# 4G.net
KiCad netlist of a schematic drawn in Altium Designer
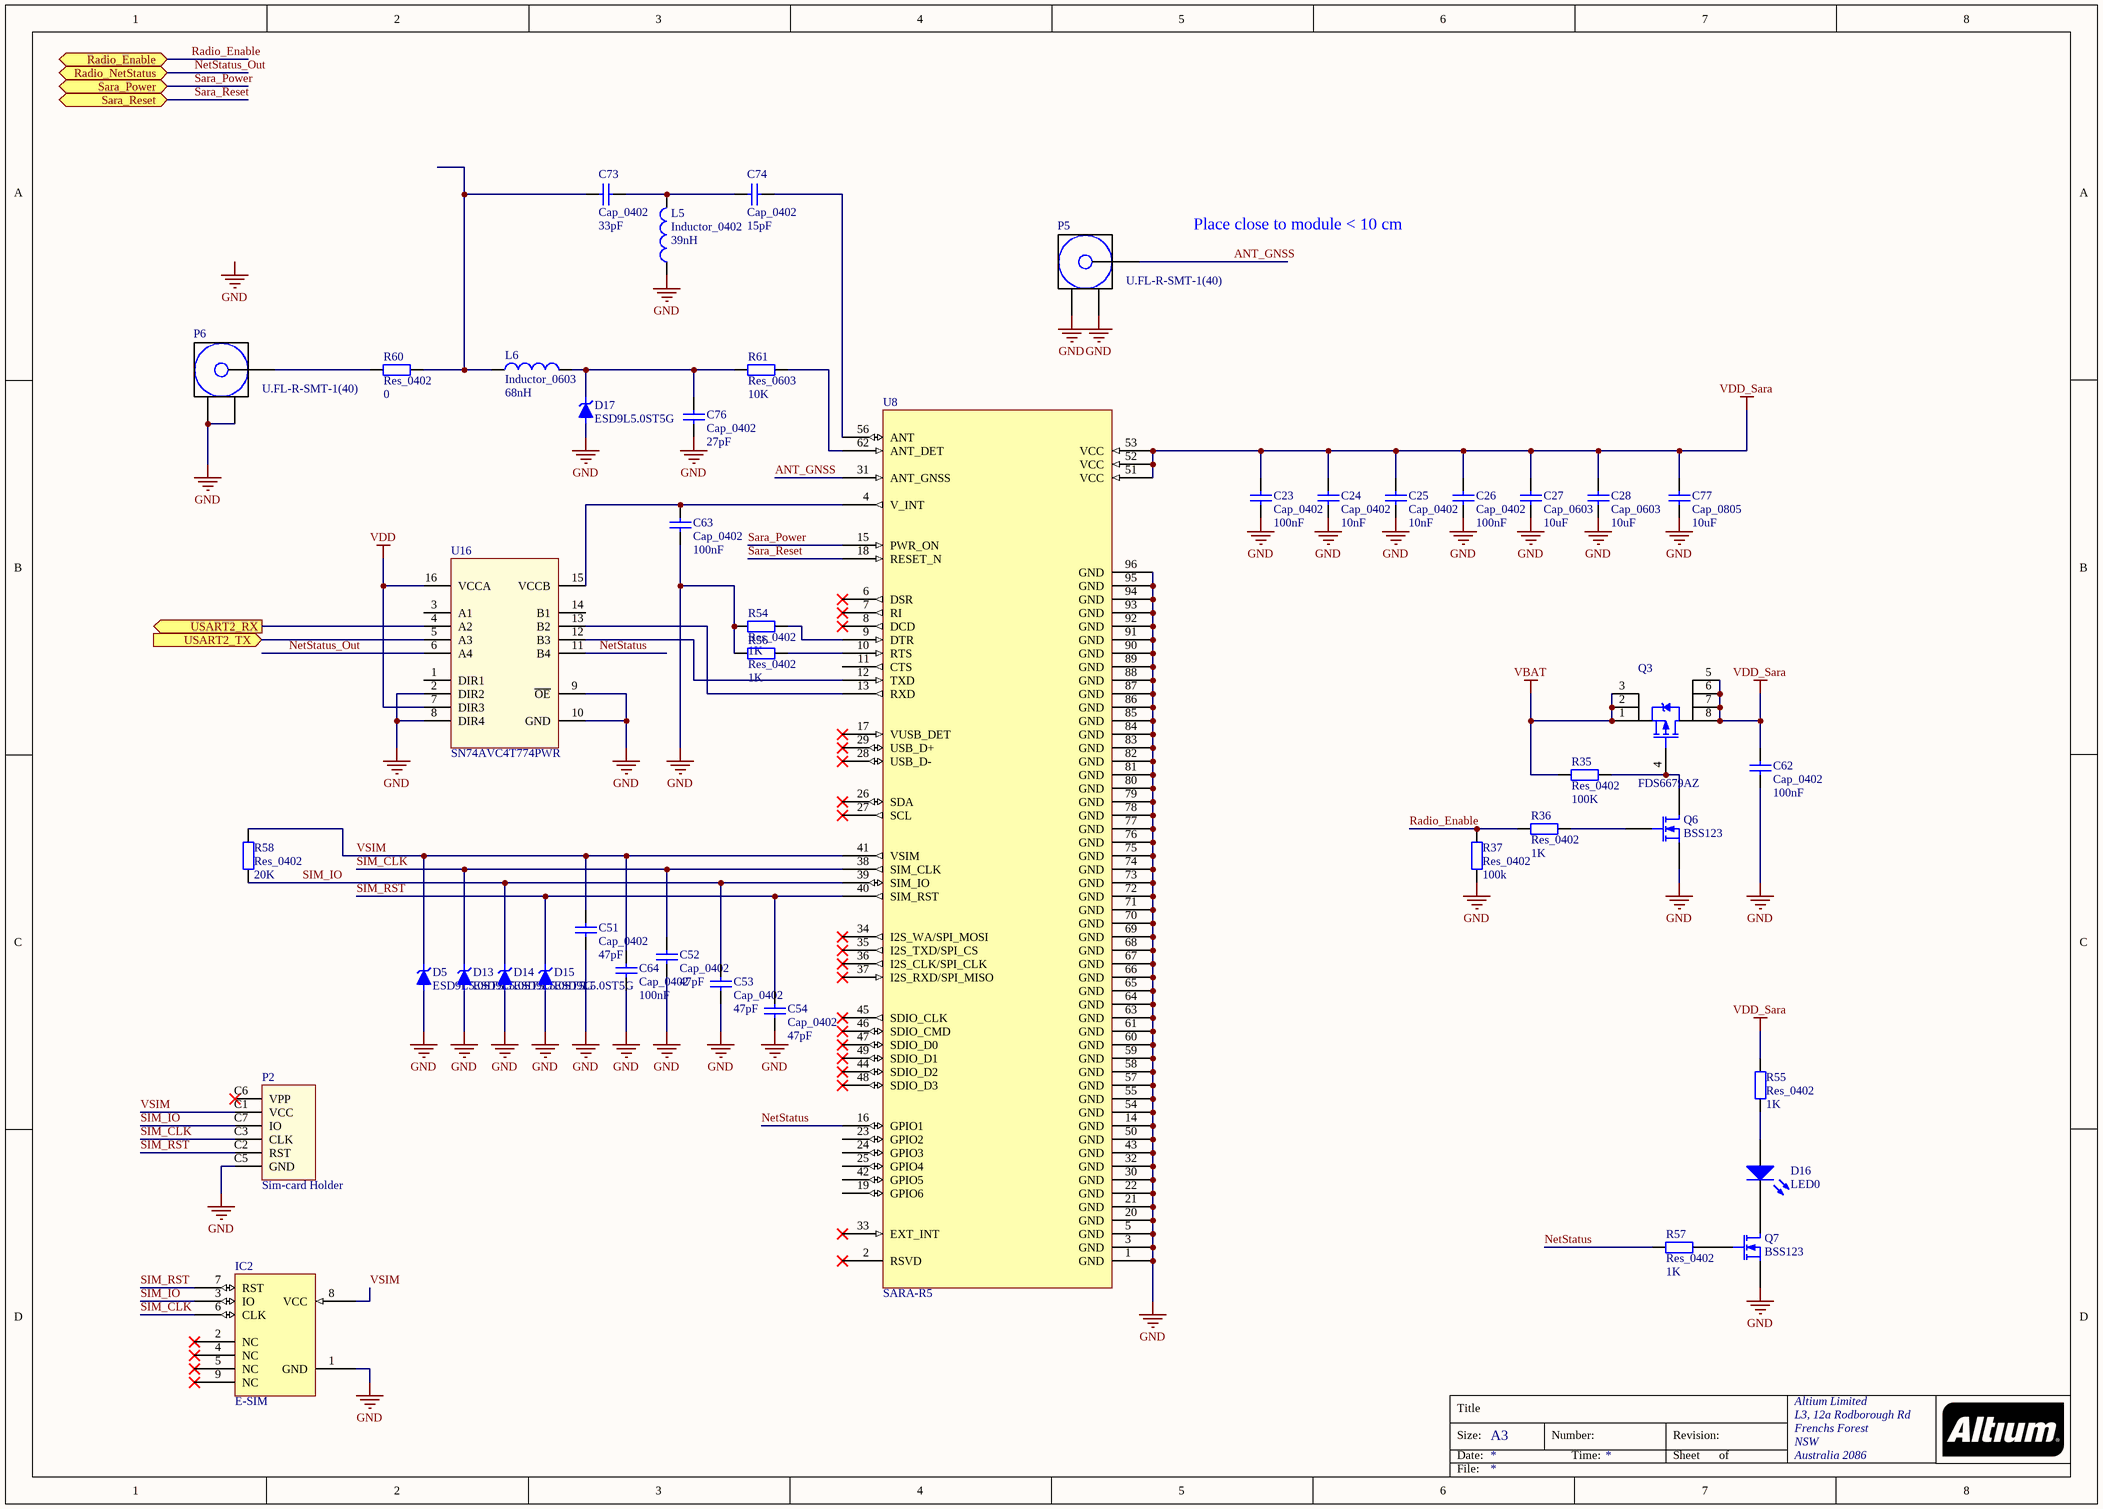
[diagram p0: 4G.SchDoc]

(export (version "E")
  (design (tool "Eeschema 10.0.6"))
  (components
    (comp (ref "C23")
      (value "Cap_0402")
      (footprint "0402")
      (description "Capacitor")
      (fields (field (name "ALTIUM_VALUE") "100nF") (field (name "PUBLISHER") "Altium Limited"))
      (libsource (lib "Schematic_Components") (part "Cap_0402"))
    )
    (comp (ref "C24")
      (value "Cap_0402")
      (footprint "0402")
      (description "Capacitor")
      (fields (field (name "ALTIUM_VALUE") "10nF") (field (name "PUBLISHER") "Altium Limited"))
      (libsource (lib "Schematic_Components") (part "Cap_0402"))
    )
    (comp (ref "C25")
      (value "Cap_0402")
      (footprint "0402")
      (description "Capacitor")
      (fields (field (name "ALTIUM_VALUE") "10nF") (field (name "PUBLISHER") "Altium Limited"))
      (libsource (lib "Schematic_Components") (part "Cap_0402"))
    )
    (comp (ref "C26")
      (value "Cap_0402")
      (footprint "0402")
      (description "Capacitor")
      (fields (field (name "ALTIUM_VALUE") "100nF") (field (name "PUBLISHER") "Altium Limited"))
      (libsource (lib "Schematic_Components") (part "Cap_0402"))
    )
    (comp (ref "C27")
      (value "Cap_0603")
      (footprint "0603")
      (description "Capacitor")
      (fields (field (name "ALTIUM_VALUE") "10uF") (field (name "PUBLISHER") "Altium Limited"))
      (libsource (lib "Schematic_Components") (part "Cap_0603"))
    )
    (comp (ref "C28")
      (value "Cap_0603")
      (footprint "0603")
      (description "Capacitor")
      (fields (field (name "ALTIUM_VALUE") "10uF") (field (name "PUBLISHER") "Altium Limited"))
      (libsource (lib "Schematic_Components") (part "Cap_0603"))
    )
    (comp (ref "C51")
      (value "Cap_0402")
      (footprint "0402")
      (description "Capacitor")
      (fields (field (name "ALTIUM_VALUE") "47pF") (field (name "PUBLISHER") "Altium Limited"))
      (libsource (lib "Schematic_Components") (part "Cap_0402"))
    )
    (comp (ref "C52")
      (value "Cap_0402")
      (footprint "0402")
      (description "Capacitor")
      (fields (field (name "ALTIUM_VALUE") "47pF") (field (name "PUBLISHER") "Altium Limited"))
      (libsource (lib "Schematic_Components") (part "Cap_0402"))
    )
    (comp (ref "C53")
      (value "Cap_0402")
      (footprint "0402")
      (description "Capacitor")
      (fields (field (name "ALTIUM_VALUE") "47pF") (field (name "PUBLISHER") "Altium Limited"))
      (libsource (lib "Schematic_Components") (part "Cap_0402"))
    )
    (comp (ref "C54")
      (value "Cap_0402")
      (footprint "0402")
      (description "Capacitor")
      (fields (field (name "ALTIUM_VALUE") "47pF") (field (name "PUBLISHER") "Altium Limited"))
      (libsource (lib "Schematic_Components") (part "Cap_0402"))
    )
    (comp (ref "C62")
      (value "Cap_0402")
      (footprint "0402")
      (description "Capacitor")
      (fields (field (name "ALTIUM_VALUE") "100nF") (field (name "PUBLISHER") "Altium Limited"))
      (libsource (lib "Schematic_Components") (part "Cap_0402"))
    )
    (comp (ref "C63")
      (value "Cap_0402")
      (footprint "0402")
      (description "Capacitor")
      (fields (field (name "ALTIUM_VALUE") "100nF") (field (name "PUBLISHER") "Altium Limited"))
      (libsource (lib "Schematic_Components") (part "Cap_0402"))
    )
    (comp (ref "C64")
      (value "Cap_0402")
      (footprint "0402")
      (description "Capacitor")
      (fields (field (name "ALTIUM_VALUE") "100nF") (field (name "PUBLISHER") "Altium Limited"))
      (libsource (lib "Schematic_Components") (part "Cap_0402"))
    )
    (comp (ref "C73")
      (value "Cap_0402")
      (footprint "0402")
      (description "Capacitor")
      (fields (field (name "ALTIUM_VALUE") "33pF") (field (name "PUBLISHER") "Altium Limited"))
      (libsource (lib "Schematic_Components") (part "Cap_0402"))
    )
    (comp (ref "C74")
      (value "Cap_0402")
      (footprint "0402")
      (description "Capacitor")
      (fields (field (name "ALTIUM_VALUE") "15pF") (field (name "PUBLISHER") "Altium Limited"))
      (libsource (lib "Schematic_Components") (part "Cap_0402"))
    )
    (comp (ref "C76")
      (value "Cap_0402")
      (footprint "0402")
      (description "Capacitor")
      (fields (field (name "ALTIUM_VALUE") "27pF") (field (name "PUBLISHER") "Altium Limited"))
      (libsource (lib "Schematic_Components") (part "Cap_0402"))
    )
    (comp (ref "C77")
      (value "Cap_0805")
      (footprint "0805")
      (description "Capacitor")
      (fields (field (name "ALTIUM_VALUE") "10uF") (field (name "PUBLISHER") "Altium Limited"))
      (libsource (lib "Schematic_Components") (part "Cap_0805"))
    )
    (comp (ref "D5")
      (value "ESD9L5.0ST5G")
      (footprint "SODFL100X40-2N")
      (description "TVS_ESD9L5-0ST5G")
      (libsource (lib "Exeger_schematic_library") (part "ESD9L5-0ST5G"))
    )
    (comp (ref "D13")
      (value "ESD9L5.0ST5G")
      (footprint "SODFL100X40-2N")
      (description "TVS_ESD9L5-0ST5G")
      (libsource (lib "Exeger_schematic_library") (part "ESD9L5-0ST5G"))
    )
    (comp (ref "D14")
      (value "ESD9L5.0ST5G")
      (footprint "SODFL100X40-2N")
      (description "TVS_ESD9L5-0ST5G")
      (libsource (lib "Exeger_schematic_library") (part "ESD9L5-0ST5G"))
    )
    (comp (ref "D15")
      (value "ESD9L5.0ST5G")
      (footprint "SODFL100X40-2N")
      (description "TVS_ESD9L5-0ST5G")
      (libsource (lib "Exeger_schematic_library") (part "ESD9L5-0ST5G"))
    )
    (comp (ref "D16")
      (value "LED0")
      (footprint "0603")
      (description "Typical INFRARED GaAs LED")
      (fields (field (name "PUBLISHER") "Altium Limited"))
      (libsource (lib "Schematic_Components") (part "LED0"))
    )
    (comp (ref "D17")
      (value "ESD9L5.0ST5G")
      (footprint "SODFL100X40-2N")
      (description "TVS_ESD9L5-0ST5G")
      (libsource (lib "Exeger_schematic_library") (part "ESD9L5-0ST5G"))
    )
    (comp (ref "IC2")
      (value "E-SIM")
      (footprint "MFF2-ESIM")
      (description "E-Sim")
      (libsource (lib "Schematic_Components") (part "E-SIM"))
    )
    (comp (ref "L5")
      (value "Inductor_0402")
      (footprint "0402")
      (description "Inductor")
      (fields (field (name "ALTIUM_VALUE") "39nH"))
      (libsource (lib "Schematic_Components") (part "Inductor_0402"))
    )
    (comp (ref "L6")
      (value "Inductor_0603")
      (footprint "0603")
      (description "Inductor")
      (fields (field (name "ALTIUM_VALUE") "68nH"))
      (libsource (lib "Schematic_Components") (part "Inductor_0603"))
    )
    (comp (ref "P2")
      (value "Sim-card Holder")
      (footprint "Sim-card Holder")
      (description "788000001_Molex")
      (libsource (lib "Exeger_schematic_library") (part "Sim-card Holder"))
    )
    (comp (ref "P5")
      (value "U.FL-R-SMT-1(40)")
      (footprint "U.FL-R-SMT-1(40)")
      (description "RF-Connector")
      (libsource (lib "Exeger_schematic_library") (part "RF-Connector"))
    )
    (comp (ref "P6")
      (value "U.FL-R-SMT-1(40)")
      (footprint "U.FL-R-SMT-1(40)")
      (description "RF-Connector")
      (libsource (lib "Exeger_schematic_library") (part "RF-Connector"))
    )
    (comp (ref "Q3")
      (value "FDS6679AZ")
      (footprint "SOIC127P600X175-8N")
      (description "Transistor, FET")
      (libsource (lib "Exeger_schematic_library") (part "FDS6679AZ"))
    )
    (comp (ref "Q6")
      (value "BSS123")
      (footprint "SOT-23")
      (description "N-Channel MOSFET")
      (fields (field (name "PUBLISHER") "Altium Limited"))
      (libsource (lib "Schematic_Components") (part "BSS123"))
    )
    (comp (ref "Q7")
      (value "BSS123")
      (footprint "SOT-23")
      (description "N-Channel MOSFET")
      (fields (field (name "PUBLISHER") "Altium Limited"))
      (libsource (lib "Schematic_Components") (part "BSS123"))
    )
    (comp (ref "R35")
      (value "Res_0402")
      (footprint "0402")
      (description "Resistor")
      (fields (field (name "ALTIUM_VALUE") "100K") (field (name "PUBLISHER") "Altium Limited"))
      (libsource (lib "") (part "Res_0402_1"))
    )
    (comp (ref "R36")
      (value "Res_0402")
      (footprint "0402")
      (description "Resistor")
      (fields (field (name "ALTIUM_VALUE") "1K") (field (name "PUBLISHER") "Altium Limited"))
      (libsource (lib "") (part "Res_0402_1"))
    )
    (comp (ref "R37")
      (value "Res_0402")
      (footprint "0402")
      (description "Resistor")
      (fields (field (name "ALTIUM_VALUE") "100k") (field (name "PUBLISHER") "Altium Limited"))
      (libsource (lib "Schematic_Components") (part "Res_0402"))
    )
    (comp (ref "R54")
      (value "Res_0402")
      (footprint "0402")
      (description "Resistor")
      (fields (field (name "ALTIUM_VALUE") "1K") (field (name "PUBLISHER") "Altium Limited"))
      (libsource (lib "") (part "Res_0402_1"))
    )
    (comp (ref "R55")
      (value "Res_0402")
      (footprint "0402")
      (description "Resistor")
      (fields (field (name "ALTIUM_VALUE") "1K") (field (name "PUBLISHER") "Altium Limited"))
      (libsource (lib "Schematic_Components") (part "Res_0402"))
    )
    (comp (ref "R56")
      (value "Res_0402")
      (footprint "0402")
      (description "Resistor")
      (fields (field (name "ALTIUM_VALUE") "1K") (field (name "PUBLISHER") "Altium Limited"))
      (libsource (lib "") (part "Res_0402_1"))
    )
    (comp (ref "R57")
      (value "Res_0402")
      (footprint "0402")
      (description "Resistor")
      (fields (field (name "ALTIUM_VALUE") "1K") (field (name "PUBLISHER") "Altium Limited"))
      (libsource (lib "") (part "Res_0402_1"))
    )
    (comp (ref "R58")
      (value "Res_0402")
      (footprint "0402")
      (description "Resistor")
      (fields (field (name "ALTIUM_VALUE") "20K") (field (name "PUBLISHER") "Altium Limited"))
      (libsource (lib "Schematic_Components") (part "Res_0402"))
    )
    (comp (ref "R60")
      (value "Res_0402")
      (footprint "0402")
      (description "Resistor")
      (fields (field (name "ALTIUM_VALUE") "0") (field (name "PUBLISHER") "Altium Limited"))
      (libsource (lib "") (part "Res_0402_1"))
    )
    (comp (ref "R61")
      (value "Res_0603")
      (footprint "0603")
      (description "Resistor")
      (fields (field (name "ALTIUM_VALUE") "10K") (field (name "PUBLISHER") "Altium Limited"))
      (libsource (lib "Schematic_Components") (part "Res_0603"))
    )
    (comp (ref "U8")
      (value "SARA-R5")
      (footprint "SARA-XX")
      (description "Sara-R5")
      (libsource (lib "Schematic_Components") (part "SARA-R5"))
    )
    (comp (ref "U16")
      (value "SN74AVC4T774PWR")
      (footprint "TSOP65P640X120-16N")
      (description "Buffer")
      (libsource (lib "Exeger_schematic_library") (part "SN74AVC4T774PWR"))
    )
  )
  (nets
    (net (code "1") (name "/ANT_GNSS") (class "Default")
      (node (ref "P5") (pin "1") (pinfunction "1_1") (pintype "passive"))
      (node (ref "U8") (pin "31") (pinfunction "ANT_GNSS_31") (pintype "input"))
    )
    (net (code "2") (name "/NetStatus") (class "Default")
      (node (ref "R57") (pin "1") (pinfunction "1_1") (pintype "passive"))
      (node (ref "U16") (pin "11") (pinfunction "B4_11") (pintype "passive"))
      (node (ref "U8") (pin "16") (pinfunction "GPIO1_16") (pintype "bidirectional"))
    )
    (net (code "3") (name "/NetStatus_Out") (class "Default")
      (node (ref "U16") (pin "6") (pinfunction "A4_6") (pintype "passive"))
    )
    (net (code "4") (name "/Radio_Enable") (class "Default")
      (node (ref "R36") (pin "1") (pinfunction "1_1") (pintype "passive"))
      (node (ref "R37") (pin "2") (pinfunction "2_2") (pintype "passive"))
    )
    (net (code "5") (name "/SIM_CLK") (class "Default")
      (node (ref "C52") (pin "2") (pinfunction "2_2") (pintype "passive"))
      (node (ref "D13") (pin "1") (pinfunction "1_1") (pintype "passive"))
      (node (ref "IC2") (pin "6") (pinfunction "CLK_6") (pintype "bidirectional"))
      (node (ref "P2") (pin "C3") (pinfunction "CLK_C3") (pintype "passive"))
      (node (ref "U8") (pin "38") (pinfunction "SIM_CLK_38") (pintype "output"))
    )
    (net (code "6") (name "/SIM_IO") (class "Default")
      (node (ref "C53") (pin "2") (pinfunction "2_2") (pintype "passive"))
      (node (ref "D14") (pin "1") (pinfunction "1_1") (pintype "passive"))
      (node (ref "IC2") (pin "3") (pinfunction "IO_3") (pintype "bidirectional"))
      (node (ref "P2") (pin "C7") (pinfunction "IO_C7") (pintype "passive"))
      (node (ref "R58") (pin "1") (pinfunction "1_1") (pintype "passive"))
      (node (ref "U8") (pin "39") (pinfunction "SIM_IO_39") (pintype "bidirectional"))
    )
    (net (code "7") (name "/SIM_RST") (class "Default")
      (node (ref "C54") (pin "2") (pinfunction "2_2") (pintype "passive"))
      (node (ref "D15") (pin "1") (pinfunction "1_1") (pintype "passive"))
      (node (ref "IC2") (pin "7") (pinfunction "RST_7") (pintype "bidirectional"))
      (node (ref "P2") (pin "C2") (pinfunction "RST_C2") (pintype "passive"))
      (node (ref "U8") (pin "40") (pinfunction "SIM_RST_40") (pintype "output"))
    )
    (net (code "8") (name "/Sara_Power") (class "Default")
      (node (ref "U8") (pin "15") (pinfunction "PWR_ON_15") (pintype "input"))
    )
    (net (code "9") (name "/Sara_Reset") (class "Default")
      (node (ref "U8") (pin "18") (pinfunction "RESET_N_18") (pintype "input"))
    )
    (net (code "10") (name "/USART2_RX") (class "Default")
      (node (ref "U16") (pin "4") (pinfunction "A2_4") (pintype "passive"))
    )
    (net (code "11") (name "/USART2_TX") (class "Default")
      (node (ref "U16") (pin "5") (pinfunction "A3_5") (pintype "passive"))
    )
    (net (code "12") (name "/VSIM") (class "Default")
      (node (ref "C51") (pin "2") (pinfunction "2_2") (pintype "passive"))
      (node (ref "C64") (pin "2") (pinfunction "2_2") (pintype "passive"))
      (node (ref "D5") (pin "1") (pinfunction "1_1") (pintype "passive"))
      (node (ref "IC2") (pin "8") (pinfunction "VCC_8") (pintype "input"))
      (node (ref "P2") (pin "C1") (pinfunction "VCC_C1") (pintype "passive"))
      (node (ref "R58") (pin "2") (pinfunction "2_2") (pintype "passive"))
      (node (ref "U8") (pin "41") (pinfunction "VSIM_41") (pintype "output"))
    )
    (net (code "13") (name "GND") (class "Default")
      (node (ref "C23") (pin "1") (pinfunction "1_1") (pintype "passive"))
      (node (ref "C24") (pin "1") (pinfunction "1_1") (pintype "passive"))
      (node (ref "C25") (pin "1") (pinfunction "1_1") (pintype "passive"))
      (node (ref "C26") (pin "1") (pinfunction "1_1") (pintype "passive"))
      (node (ref "C27") (pin "1") (pinfunction "1_1") (pintype "passive"))
      (node (ref "C28") (pin "1") (pinfunction "1_1") (pintype "passive"))
      (node (ref "C51") (pin "1") (pinfunction "1_1") (pintype "passive"))
      (node (ref "C52") (pin "1") (pinfunction "1_1") (pintype "passive"))
      (node (ref "C53") (pin "1") (pinfunction "1_1") (pintype "passive"))
      (node (ref "C54") (pin "1") (pinfunction "1_1") (pintype "passive"))
      (node (ref "C62") (pin "1") (pinfunction "1_1") (pintype "passive"))
      (node (ref "C63") (pin "1") (pinfunction "1_1") (pintype "passive"))
      (node (ref "C64") (pin "1") (pinfunction "1_1") (pintype "passive"))
      (node (ref "C76") (pin "1") (pinfunction "1_1") (pintype "passive"))
      (node (ref "C77") (pin "1") (pinfunction "1_1") (pintype "passive"))
      (node (ref "D13") (pin "2") (pinfunction "2_2") (pintype "passive"))
      (node (ref "D14") (pin "2") (pinfunction "2_2") (pintype "passive"))
      (node (ref "D15") (pin "2") (pinfunction "2_2") (pintype "passive"))
      (node (ref "D17") (pin "2") (pinfunction "2_2") (pintype "passive"))
      (node (ref "D5") (pin "2") (pinfunction "2_2") (pintype "passive"))
      (node (ref "IC2") (pin "1") (pinfunction "GND_1") (pintype "passive"))
      (node (ref "L5") (pin "1") (pinfunction "1_1") (pintype "passive"))
      (node (ref "P2") (pin "C5") (pinfunction "GND_C5") (pintype "passive"))
      (node (ref "P5") (pin "2") (pinfunction "2_2") (pintype "passive"))
      (node (ref "P5") (pin "3") (pinfunction "3_3") (pintype "passive"))
      (node (ref "P6") (pin "2") (pinfunction "2_2") (pintype "passive"))
      (node (ref "P6") (pin "3") (pinfunction "3_3") (pintype "passive"))
      (node (ref "Q6") (pin "2") (pinfunction "S_2") (pintype "passive"))
      (node (ref "Q7") (pin "2") (pinfunction "S_2") (pintype "passive"))
      (node (ref "R37") (pin "1") (pinfunction "1_1") (pintype "passive"))
      (node (ref "R54") (pin "1") (pinfunction "1_1") (pintype "passive"))
      (node (ref "R56") (pin "1") (pinfunction "1_1") (pintype "passive"))
      (node (ref "U16") (pin "10") (pinfunction "GND_10") (pintype "passive"))
      (node (ref "U16") (pin "2") (pinfunction "DIR2_2") (pintype "passive"))
      (node (ref "U16") (pin "8") (pinfunction "DIR4_8") (pintype "passive"))
      (node (ref "U16") (pin "9") (pinfunction "~{OE}_9") (pintype "passive"))
      (node (ref "U8") (pin "1") (pinfunction "GND_1") (pintype "passive"))
      (node (ref "U8") (pin "14") (pinfunction "GND_14") (pintype "passive"))
      (node (ref "U8") (pin "20") (pinfunction "GND_20") (pintype "passive"))
      (node (ref "U8") (pin "21") (pinfunction "GND_21") (pintype "passive"))
      (node (ref "U8") (pin "22") (pinfunction "GND_22") (pintype "passive"))
      (node (ref "U8") (pin "3") (pinfunction "GND_3") (pintype "passive"))
      (node (ref "U8") (pin "30") (pinfunction "GND_30") (pintype "passive"))
      (node (ref "U8") (pin "32") (pinfunction "GND_32") (pintype "passive"))
      (node (ref "U8") (pin "43") (pinfunction "GND_43") (pintype "passive"))
      (node (ref "U8") (pin "5") (pinfunction "GND_5") (pintype "passive"))
      (node (ref "U8") (pin "50") (pinfunction "GND_50") (pintype "passive"))
      (node (ref "U8") (pin "54") (pinfunction "GND_54") (pintype "passive"))
      (node (ref "U8") (pin "55") (pinfunction "GND_55") (pintype "passive"))
      (node (ref "U8") (pin "57") (pinfunction "GND_57") (pintype "passive"))
      (node (ref "U8") (pin "58") (pinfunction "GND_58") (pintype "passive"))
      (node (ref "U8") (pin "59") (pinfunction "GND_59") (pintype "passive"))
      (node (ref "U8") (pin "60") (pinfunction "GND_60") (pintype "passive"))
      (node (ref "U8") (pin "61") (pinfunction "GND_61") (pintype "passive"))
      (node (ref "U8") (pin "63") (pinfunction "GND_63") (pintype "passive"))
      (node (ref "U8") (pin "64") (pinfunction "GND_64") (pintype "passive"))
      (node (ref "U8") (pin "65") (pinfunction "GND_65") (pintype "passive"))
      (node (ref "U8") (pin "66") (pinfunction "GND_66") (pintype "passive"))
      (node (ref "U8") (pin "67") (pinfunction "GND_67") (pintype "passive"))
      (node (ref "U8") (pin "68") (pinfunction "GND_68") (pintype "passive"))
      (node (ref "U8") (pin "69") (pinfunction "GND_69") (pintype "passive"))
      (node (ref "U8") (pin "70") (pinfunction "GND_70") (pintype "passive"))
      (node (ref "U8") (pin "71") (pinfunction "GND_71") (pintype "passive"))
      (node (ref "U8") (pin "72") (pinfunction "GND_72") (pintype "passive"))
      (node (ref "U8") (pin "73") (pinfunction "GND_73") (pintype "passive"))
      (node (ref "U8") (pin "74") (pinfunction "GND_74") (pintype "passive"))
      (node (ref "U8") (pin "75") (pinfunction "GND_75") (pintype "passive"))
      (node (ref "U8") (pin "76") (pinfunction "GND_76") (pintype "passive"))
      (node (ref "U8") (pin "77") (pinfunction "GND_77") (pintype "passive"))
      (node (ref "U8") (pin "78") (pinfunction "GND_78") (pintype "passive"))
      (node (ref "U8") (pin "79") (pinfunction "GND_79") (pintype "passive"))
      (node (ref "U8") (pin "80") (pinfunction "GND_80") (pintype "passive"))
      (node (ref "U8") (pin "81") (pinfunction "GND_81") (pintype "passive"))
      (node (ref "U8") (pin "82") (pinfunction "GND_82") (pintype "passive"))
      (node (ref "U8") (pin "83") (pinfunction "GND_83") (pintype "passive"))
      (node (ref "U8") (pin "84") (pinfunction "GND_84") (pintype "passive"))
      (node (ref "U8") (pin "85") (pinfunction "GND_85") (pintype "passive"))
      (node (ref "U8") (pin "86") (pinfunction "GND_86") (pintype "passive"))
      (node (ref "U8") (pin "87") (pinfunction "GND_87") (pintype "passive"))
      (node (ref "U8") (pin "88") (pinfunction "GND_88") (pintype "passive"))
      (node (ref "U8") (pin "89") (pinfunction "GND_89") (pintype "passive"))
      (node (ref "U8") (pin "90") (pinfunction "GND_90") (pintype "passive"))
      (node (ref "U8") (pin "91") (pinfunction "GND_91") (pintype "passive"))
      (node (ref "U8") (pin "92") (pinfunction "GND_92") (pintype "passive"))
      (node (ref "U8") (pin "93") (pinfunction "GND_93") (pintype "passive"))
      (node (ref "U8") (pin "94") (pinfunction "GND_94") (pintype "passive"))
      (node (ref "U8") (pin "95") (pinfunction "GND_95") (pintype "passive"))
      (node (ref "U8") (pin "96") (pinfunction "GND_96") (pintype "passive"))
    )
    (net (code "14") (name "Net-(C73-Pad1)") (class "Default")
      (node (ref "C73") (pin "1") (pinfunction "1_1") (pintype "passive"))
      (node (ref "C74") (pin "1") (pinfunction "1_1") (pintype "passive"))
      (node (ref "L5") (pin "2") (pinfunction "2_2") (pintype "passive"))
    )
    (net (code "15") (name "Net-(C73-Pad2)") (class "Default")
      (node (ref "C73") (pin "2") (pinfunction "2_2") (pintype "passive"))
      (node (ref "L6") (pin "1") (pinfunction "1_1") (pintype "passive"))
      (node (ref "R60") (pin "2") (pinfunction "2_2") (pintype "passive"))
    )
    (net (code "16") (name "Net-(C76-Pad2)") (class "Default")
      (node (ref "C76") (pin "2") (pinfunction "2_2") (pintype "passive"))
      (node (ref "D17") (pin "1") (pinfunction "1_1") (pintype "passive"))
      (node (ref "L6") (pin "2") (pinfunction "2_2") (pintype "passive"))
      (node (ref "R61") (pin "1") (pinfunction "1_1") (pintype "passive"))
    )
    (net (code "17") (name "Net-(D16-A)") (class "Default")
      (node (ref "D16") (pin "2") (pinfunction "A_2") (pintype "passive"))
      (node (ref "R55") (pin "1") (pinfunction "1_1") (pintype "passive"))
    )
    (net (code "18") (name "Net-(D16-K)") (class "Default")
      (node (ref "D16") (pin "1") (pinfunction "K_1") (pintype "passive"))
      (node (ref "Q7") (pin "3") (pinfunction "D_3") (pintype "passive"))
    )
    (net (code "19") (name "Net-(P6-Pad1)") (class "Default")
      (node (ref "P6") (pin "1") (pinfunction "1_1") (pintype "passive"))
      (node (ref "R60") (pin "1") (pinfunction "1_1") (pintype "passive"))
    )
    (net (code "20") (name "Net-(Q3-G)") (class "Default")
      (node (ref "Q3") (pin "4") (pinfunction "G_4") (pintype "passive"))
      (node (ref "Q6") (pin "3") (pinfunction "D_3") (pintype "passive"))
      (node (ref "R35") (pin "2") (pinfunction "2_2") (pintype "passive"))
    )
    (net (code "21") (name "Net-(Q6-G)") (class "Default")
      (node (ref "Q6") (pin "1") (pinfunction "G_1") (pintype "passive"))
      (node (ref "R36") (pin "2") (pinfunction "2_2") (pintype "passive"))
    )
    (net (code "22") (name "Net-(Q7-G)") (class "Default")
      (node (ref "Q7") (pin "1") (pinfunction "G_1") (pintype "passive"))
      (node (ref "R57") (pin "2") (pinfunction "2_2") (pintype "passive"))
    )
    (net (code "23") (name "Net-(U8-ANT)") (class "Default")
      (node (ref "C74") (pin "2") (pinfunction "2_2") (pintype "passive"))
      (node (ref "U8") (pin "56") (pinfunction "ANT_56") (pintype "bidirectional"))
    )
    (net (code "24") (name "Net-(U8-ANT_DET)") (class "Default")
      (node (ref "R61") (pin "2") (pinfunction "2_2") (pintype "passive"))
      (node (ref "U8") (pin "62") (pinfunction "ANT_DET_62") (pintype "input"))
    )
    (net (code "25") (name "Net-(U8-DTR)") (class "Default")
      (node (ref "R54") (pin "2") (pinfunction "2_2") (pintype "passive"))
      (node (ref "U8") (pin "9") (pinfunction "DTR_9") (pintype "input"))
    )
    (net (code "26") (name "Net-(U8-RTS)") (class "Default")
      (node (ref "R56") (pin "2") (pinfunction "2_2") (pintype "passive"))
      (node (ref "U8") (pin "10") (pinfunction "RTS_10") (pintype "input"))
    )
    (net (code "27") (name "Net-(U16-B2)") (class "Default")
      (node (ref "U16") (pin "13") (pinfunction "B2_13") (pintype "passive"))
      (node (ref "U8") (pin "13") (pinfunction "RXD_13") (pintype "output"))
    )
    (net (code "28") (name "Net-(U16-B3)") (class "Default")
      (node (ref "U16") (pin "12") (pinfunction "B3_12") (pintype "passive"))
      (node (ref "U8") (pin "12") (pinfunction "TXD_12") (pintype "input"))
    )
    (net (code "29") (name "Net-(U16-VCCB)") (class "Default")
      (node (ref "C63") (pin "2") (pinfunction "2_2") (pintype "passive"))
      (node (ref "U16") (pin "15") (pinfunction "VCCB_15") (pintype "passive"))
      (node (ref "U8") (pin "4") (pinfunction "V_INT_4") (pintype "output"))
    )
    (net (code "30") (name "VBAT") (class "Default")
      (node (ref "Q3") (pin "1") (pinfunction "S_1") (pintype "passive"))
      (node (ref "Q3") (pin "2") (pinfunction "S_2") (pintype "passive"))
      (node (ref "Q3") (pin "3") (pinfunction "S_3") (pintype "passive"))
      (node (ref "R35") (pin "1") (pinfunction "1_1") (pintype "passive"))
    )
    (net (code "31") (name "VDD") (class "Default")
      (node (ref "U16") (pin "16") (pinfunction "VCCA_16") (pintype "passive"))
      (node (ref "U16") (pin "7") (pinfunction "DIR3_7") (pintype "passive"))
    )
    (net (code "32") (name "VDD_Sara") (class "Default")
      (node (ref "C23") (pin "2") (pinfunction "2_2") (pintype "passive"))
      (node (ref "C24") (pin "2") (pinfunction "2_2") (pintype "passive"))
      (node (ref "C25") (pin "2") (pinfunction "2_2") (pintype "passive"))
      (node (ref "C26") (pin "2") (pinfunction "2_2") (pintype "passive"))
      (node (ref "C27") (pin "2") (pinfunction "2_2") (pintype "passive"))
      (node (ref "C28") (pin "2") (pinfunction "2_2") (pintype "passive"))
      (node (ref "C62") (pin "2") (pinfunction "2_2") (pintype "passive"))
      (node (ref "C77") (pin "2") (pinfunction "2_2") (pintype "passive"))
      (node (ref "Q3") (pin "5") (pinfunction "D_5") (pintype "passive"))
      (node (ref "Q3") (pin "6") (pinfunction "D_6") (pintype "passive"))
      (node (ref "Q3") (pin "7") (pinfunction "D_7") (pintype "passive"))
      (node (ref "Q3") (pin "8") (pinfunction "D_8") (pintype "passive"))
      (node (ref "R55") (pin "2") (pinfunction "2_2") (pintype "passive"))
      (node (ref "U8") (pin "51") (pinfunction "VCC_51") (pintype "input"))
      (node (ref "U8") (pin "52") (pinfunction "VCC_52") (pintype "input"))
      (node (ref "U8") (pin "53") (pinfunction "VCC_53") (pintype "input"))
    )
    (net (code "33") (name "unconnected-(IC2-NC-Pad2)") (class "Default")
      (node (ref "IC2") (pin "2") (pinfunction "NC_2") (pintype "passive+no_connect"))
    )
    (net (code "34") (name "unconnected-(IC2-NC-Pad4)") (class "Default")
      (node (ref "IC2") (pin "4") (pinfunction "NC_4") (pintype "passive+no_connect"))
    )
    (net (code "35") (name "unconnected-(IC2-NC-Pad5)") (class "Default")
      (node (ref "IC2") (pin "5") (pinfunction "NC_5") (pintype "passive+no_connect"))
    )
    (net (code "36") (name "unconnected-(IC2-NC-Pad9)") (class "Default")
      (node (ref "IC2") (pin "9") (pinfunction "NC_9") (pintype "passive+no_connect"))
    )
    (net (code "37") (name "unconnected-(P2-VPP-PadC6)") (class "Default")
      (node (ref "P2") (pin "C6") (pinfunction "VPP_C6") (pintype "passive+no_connect"))
    )
    (net (code "38") (name "unconnected-(U8-CTS-Pad11)") (class "Default")
      (node (ref "U8") (pin "11") (pinfunction "CTS_11") (pintype "output"))
    )
    (net (code "39") (name "unconnected-(U8-DCD-Pad8)") (class "Default")
      (node (ref "U8") (pin "8") (pinfunction "DCD_8") (pintype "output+no_connect"))
    )
    (net (code "40") (name "unconnected-(U8-DSR-Pad6)") (class "Default")
      (node (ref "U8") (pin "6") (pinfunction "DSR_6") (pintype "output+no_connect"))
    )
    (net (code "41") (name "unconnected-(U8-EXT_INT-Pad33)") (class "Default")
      (node (ref "U8") (pin "33") (pinfunction "EXT_INT_33") (pintype "input+no_connect"))
    )
    (net (code "42") (name "unconnected-(U8-GPIO2-Pad23)") (class "Default")
      (node (ref "U8") (pin "23") (pinfunction "GPIO2_23") (pintype "bidirectional"))
    )
    (net (code "43") (name "unconnected-(U8-GPIO3-Pad24)") (class "Default")
      (node (ref "U8") (pin "24") (pinfunction "GPIO3_24") (pintype "bidirectional"))
    )
    (net (code "44") (name "unconnected-(U8-GPIO4-Pad25)") (class "Default")
      (node (ref "U8") (pin "25") (pinfunction "GPIO4_25") (pintype "bidirectional"))
    )
    (net (code "45") (name "unconnected-(U8-GPIO5-Pad42)") (class "Default")
      (node (ref "U8") (pin "42") (pinfunction "GPIO5_42") (pintype "bidirectional"))
    )
    (net (code "46") (name "unconnected-(U8-GPIO6-Pad19)") (class "Default")
      (node (ref "U8") (pin "19") (pinfunction "GPIO6_19") (pintype "bidirectional"))
    )
    (net (code "47") (name "unconnected-(U8-I2S_CLK{slash}SPI_CLK-Pad36)") (class "Default")
      (node (ref "U8") (pin "36") (pinfunction "I2S_CLK/SPI_CLK_36") (pintype "output+no_connect"))
    )
    (net (code "48") (name "unconnected-(U8-I2S_RXD{slash}SPI_MISO-Pad37)") (class "Default")
      (node (ref "U8") (pin "37") (pinfunction "I2S_RXD/SPI_MISO_37") (pintype "input+no_connect"))
    )
    (net (code "49") (name "unconnected-(U8-I2S_TXD{slash}SPI_CS-Pad35)") (class "Default")
      (node (ref "U8") (pin "35") (pinfunction "I2S_TXD/SPI_CS_35") (pintype "output+no_connect"))
    )
    (net (code "50") (name "unconnected-(U8-I2S_WA{slash}SPI_MOSI-Pad34)") (class "Default")
      (node (ref "U8") (pin "34") (pinfunction "I2S_WA/SPI_MOSI_34") (pintype "output+no_connect"))
    )
    (net (code "51") (name "unconnected-(U8-RI-Pad7)") (class "Default")
      (node (ref "U8") (pin "7") (pinfunction "RI_7") (pintype "output+no_connect"))
    )
    (net (code "52") (name "unconnected-(U8-RSVD-Pad2)") (class "Default")
      (node (ref "U8") (pin "2") (pinfunction "RSVD_2") (pintype "passive+no_connect"))
    )
    (net (code "53") (name "unconnected-(U8-SCL-Pad27)") (class "Default")
      (node (ref "U8") (pin "27") (pinfunction "SCL_27") (pintype "output+no_connect"))
    )
    (net (code "54") (name "unconnected-(U8-SDA-Pad26)") (class "Default")
      (node (ref "U8") (pin "26") (pinfunction "SDA_26") (pintype "bidirectional+no_connect"))
    )
    (net (code "55") (name "unconnected-(U8-SDIO_CLK-Pad45)") (class "Default")
      (node (ref "U8") (pin "45") (pinfunction "SDIO_CLK_45") (pintype "output+no_connect"))
    )
    (net (code "56") (name "unconnected-(U8-SDIO_CMD-Pad46)") (class "Default")
      (node (ref "U8") (pin "46") (pinfunction "SDIO_CMD_46") (pintype "bidirectional+no_connect"))
    )
    (net (code "57") (name "unconnected-(U8-SDIO_D0-Pad47)") (class "Default")
      (node (ref "U8") (pin "47") (pinfunction "SDIO_D0_47") (pintype "bidirectional+no_connect"))
    )
    (net (code "58") (name "unconnected-(U8-SDIO_D1-Pad49)") (class "Default")
      (node (ref "U8") (pin "49") (pinfunction "SDIO_D1_49") (pintype "bidirectional+no_connect"))
    )
    (net (code "59") (name "unconnected-(U8-SDIO_D2-Pad44)") (class "Default")
      (node (ref "U8") (pin "44") (pinfunction "SDIO_D2_44") (pintype "bidirectional+no_connect"))
    )
    (net (code "60") (name "unconnected-(U8-SDIO_D3-Pad48)") (class "Default")
      (node (ref "U8") (pin "48") (pinfunction "SDIO_D3_48") (pintype "bidirectional+no_connect"))
    )
    (net (code "61") (name "unconnected-(U8-USB_D+-Pad29)") (class "Default")
      (node (ref "U8") (pin "29") (pinfunction "USB_D+_29") (pintype "bidirectional+no_connect"))
    )
    (net (code "62") (name "unconnected-(U8-USB_D--Pad28)") (class "Default")
      (node (ref "U8") (pin "28") (pinfunction "USB_D-_28") (pintype "bidirectional+no_connect"))
    )
    (net (code "63") (name "unconnected-(U8-VUSB_DET-Pad17)") (class "Default")
      (node (ref "U8") (pin "17") (pinfunction "VUSB_DET_17") (pintype "input+no_connect"))
    )
    (net (code "64") (name "unconnected-(U16-A1-Pad3)") (class "Default")
      (node (ref "U16") (pin "3") (pinfunction "A1_3") (pintype "passive"))
    )
    (net (code "65") (name "unconnected-(U16-B1-Pad14)") (class "Default")
      (node (ref "U16") (pin "14") (pinfunction "B1_14") (pintype "passive"))
    )
    (net (code "66") (name "unconnected-(U16-DIR1-Pad1)") (class "Default")
      (node (ref "U16") (pin "1") (pinfunction "DIR1_1") (pintype "passive"))
    )
  )
)
